# tick-mini-mk-1_0.net
KiCad netlist of a schematic drawn in EAGLE
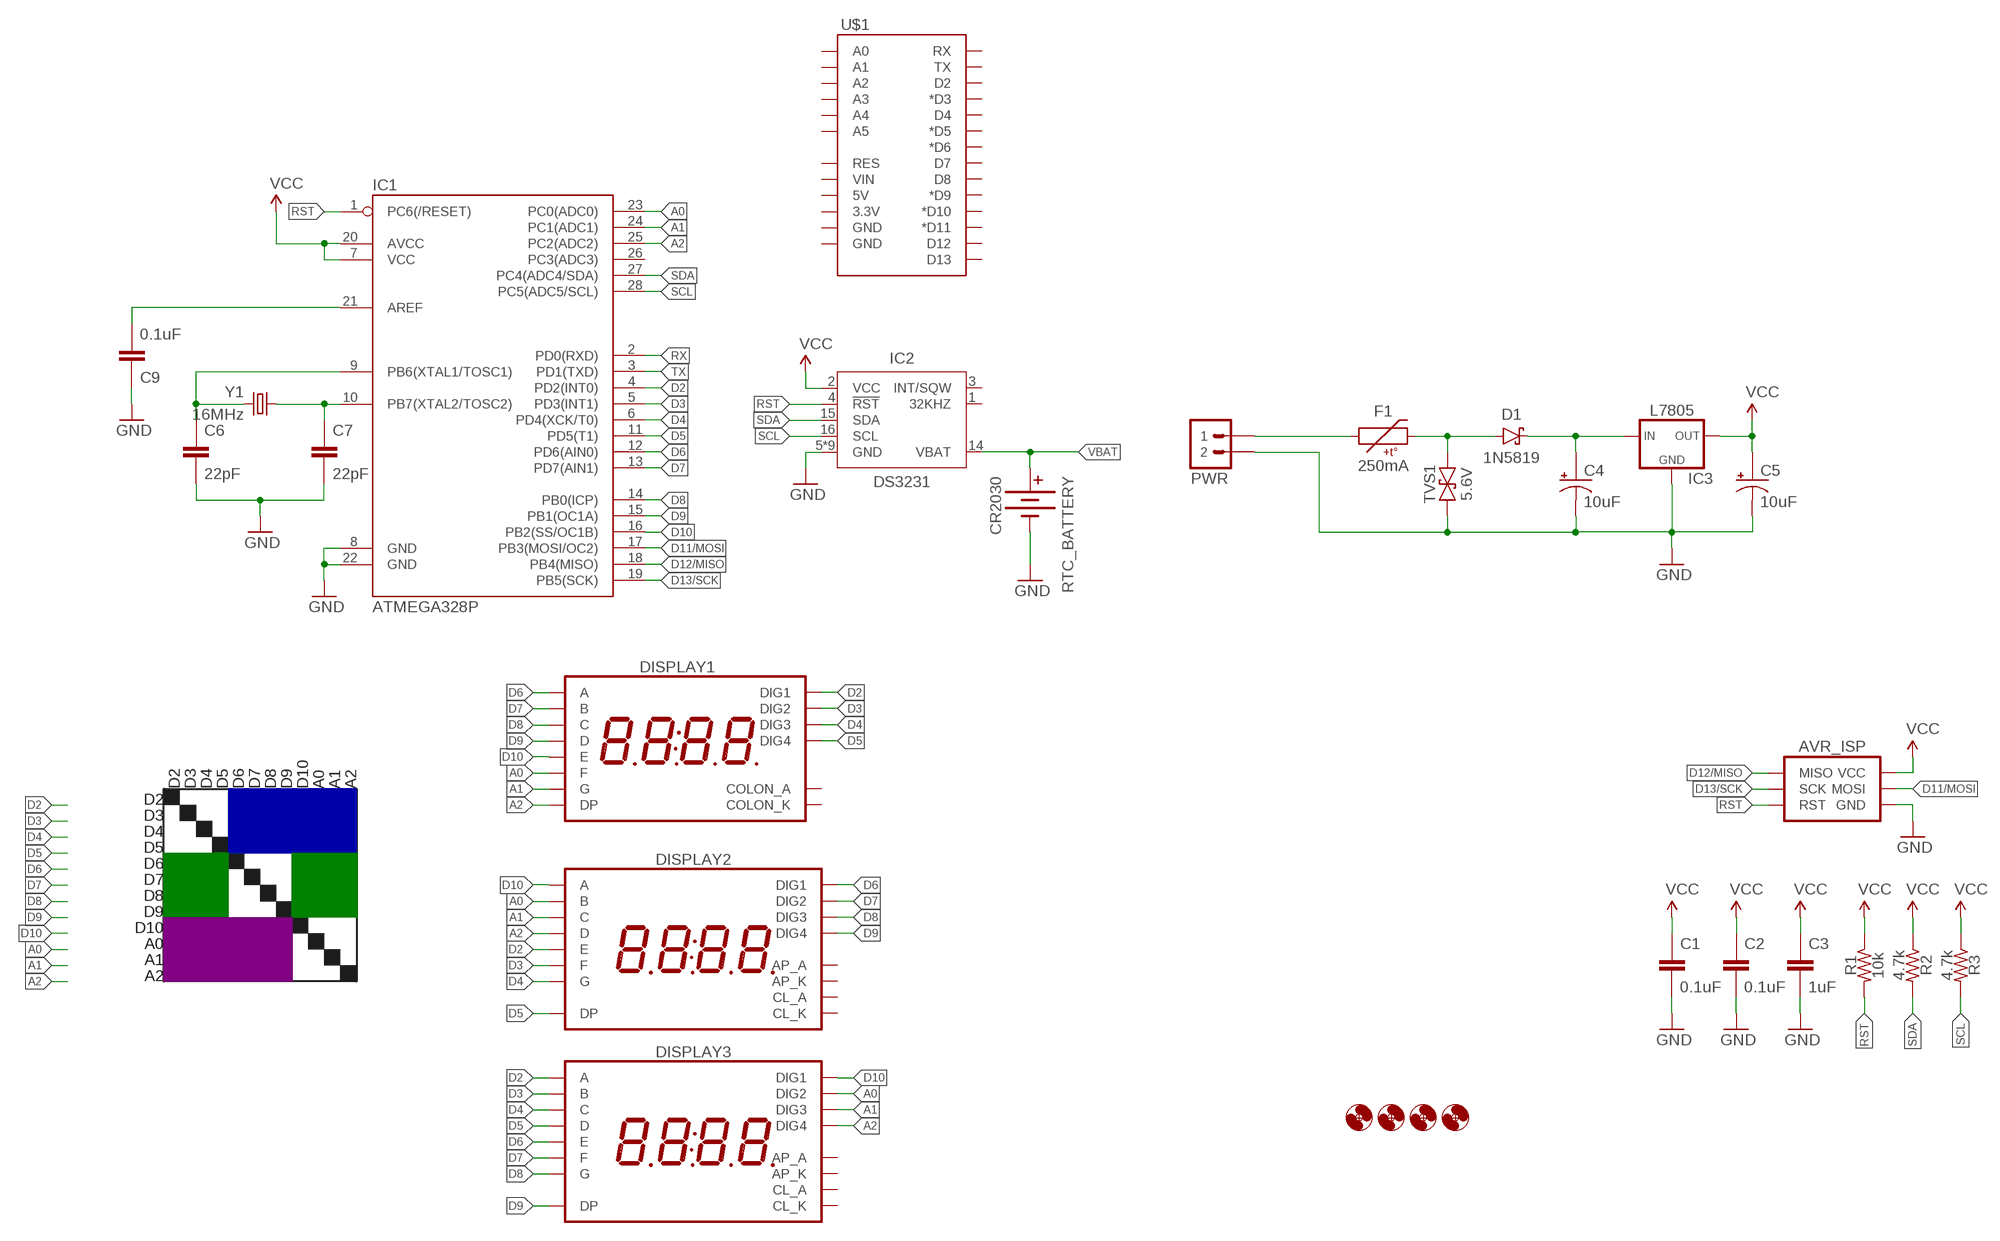
[diagram p0: schematic, sheet 1]

(export (version "E")
  (design (tool "Eeschema 10.0.6"))
  (components
    (comp (ref "AVR_ISP")
      (value "AVR_SPI_PRG_6PTH")
      (footprint "eagle-import:2X3")
      (libsource (lib "eagle-import") (part "AVR_SPI_PRG_6PTH"))
    )
    (comp (ref "C1")
      (value "0.1uF")
      (footprint "eagle-import:C025-024X044")
      (libsource (lib "eagle-import") (part "CAPACITOR-CERAMIC025-024X044"))
    )
    (comp (ref "C2")
      (value "0.1uF")
      (footprint "eagle-import:C025-024X044")
      (libsource (lib "eagle-import") (part "CAPACITOR-CERAMIC025-024X044"))
    )
    (comp (ref "C3")
      (value "1uF")
      (footprint "eagle-import:C025-024X044")
      (libsource (lib "eagle-import") (part "CAPACITOR-CERAMIC025-024X044"))
    )
    (comp (ref "C4")
      (value "10uF")
      (footprint "eagle-import:E2-5")
      (libsource (lib "eagle-import") (part "CAPACITOR-POLARIZEDE2-5"))
    )
    (comp (ref "C5")
      (value "10uF")
      (footprint "eagle-import:E2-5")
      (libsource (lib "eagle-import") (part "CAPACITOR-POLARIZEDE2-5"))
    )
    (comp (ref "C6")
      (value "22pF")
      (footprint "eagle-import:C025-024X044")
      (libsource (lib "eagle-import") (part "CAPACITOR-CERAMIC025-024X044"))
    )
    (comp (ref "C7")
      (value "22pF")
      (footprint "eagle-import:C025-024X044")
      (libsource (lib "eagle-import") (part "CAPACITOR-CERAMIC025-024X044"))
    )
    (comp (ref "C9")
      (value "0.1uF")
      (footprint "eagle-import:C025-024X044")
      (libsource (lib "eagle-import") (part "CAPACITOR-CERAMIC025-024X044"))
    )
    (comp (ref "D1")
      (value "1N5819")
      (footprint "eagle-import:DIODE-10.16MM")
      (libsource (lib "eagle-import") (part "DIODE-SCHOTTKYPTH-10.16MM"))
    )
    (comp (ref "DISPLAY1")
      (value "7SEG_4DIGIT_COLON14.2MM-CC")
      (footprint "eagle-import:7SEG_4DIG_0.56IN_14MM_ADAFRUIT")
      (libsource (lib "eagle-import") (part "7SEG_4DIGIT_COLON14.2MM-CC"))
    )
    (comp (ref "DISPLAY2")
      (value "7SEG_4DIGIT_COLON_APOS")
      (footprint "eagle-import:7SEG_4DIG_10MM")
      (libsource (lib "eagle-import") (part "7SEG_4DIGIT_COLON_APOS"))
    )
    (comp (ref "DISPLAY3")
      (value "7SEG_4DIGIT_COLON_APOS")
      (footprint "eagle-import:7SEG_4DIG_10MM")
      (libsource (lib "eagle-import") (part "7SEG_4DIGIT_COLON_APOS"))
    )
    (comp (ref "F1")
      (value "250mA")
      (footprint "eagle-import:PTC-PTH-5.08MM")
      (libsource (lib "eagle-import") (part "PTCPTH-5.08MM"))
    )
    (comp (ref "H1")
      (value "HOLE#2")
      (footprint "eagle-import:HOLE-#2")
      (libsource (lib "eagle-import") (part "HOLE#2"))
    )
    (comp (ref "H2")
      (value "HOLE#2")
      (footprint "eagle-import:HOLE-#2")
      (libsource (lib "eagle-import") (part "HOLE#2"))
    )
    (comp (ref "H3")
      (value "HOLE#2")
      (footprint "eagle-import:HOLE-#2")
      (libsource (lib "eagle-import") (part "HOLE#2"))
    )
    (comp (ref "H4")
      (value "HOLE#2")
      (footprint "eagle-import:HOLE-#2")
      (libsource (lib "eagle-import") (part "HOLE#2"))
    )
    (comp (ref "IC1")
      (value "ATMEGA328P")
      (footprint "eagle-import:DIL28-3")
      (libsource (lib "eagle-import") (part "ATMEGA328P_PDIP"))
    )
    (comp (ref "IC2")
      (value "DS3231")
      (footprint "eagle-import:SO16W")
      (libsource (lib "eagle-import") (part "DS3231"))
    )
    (comp (ref "IC3")
      (value "L7805")
      (footprint "eagle-import:TO-92-AMMO")
      (libsource (lib "eagle-import") (part "V_REG_78XXTO-92-INLINE"))
    )
    (comp (ref "PWR")
      (value "M02JST-PTH-VERT")
      (footprint "eagle-import:JST-2-PH-VERT-PTH")
      (libsource (lib "eagle-import") (part "M02JST-PTH-VERT"))
    )
    (comp (ref "R1")
      (value "10k")
      (footprint "eagle-import:RESISTOR-AXIAL-PTH-7.62MM")
      (libsource (lib "eagle-import") (part "RESISTORPTH-AXIAL-7.62MM"))
    )
    (comp (ref "R2")
      (value "4.7k")
      (footprint "eagle-import:RESISTOR-AXIAL-PTH-6.35MM")
      (libsource (lib "eagle-import") (part "RESISTORPTH-AXIAL-6.35MM"))
    )
    (comp (ref "R3")
      (value "4.7k")
      (footprint "eagle-import:RESISTOR-AXIAL-PTH-6.35MM")
      (libsource (lib "eagle-import") (part "RESISTORPTH-AXIAL-6.35MM"))
    )
    (comp (ref "RTC_BATTERY")
      (value "CR2030")
      (footprint "eagle-import:BATTCON_12MM")
      (libsource (lib "eagle-import") (part "BATTERY12MM"))
    )
    (comp (ref "TVS1")
      (value "5.6V")
      (footprint "eagle-import:DO-41-TVS-BI-10.16MM")
      (libsource (lib "eagle-import") (part "TVSDO-41-10.16MM"))
    )
    (comp (ref "U$1")
      (value "ARDUINO_SHIELD_SMALLER")
      (footprint "eagle-import:ARDUINO_SHIELD_NOOUTLINE_INSIDE_SMALLER")
      (libsource (lib "eagle-import") (part "ARDUINO_SHIELD_SMALLER"))
    )
    (comp (ref "Y1")
      (value "16MHz")
      (footprint "eagle-import:HC49U-V")
      (libsource (lib "eagle-import") (part "CRYSTALHC49UV"))
    )
  )
  (nets
    (net (code "1") (name "A0") (class "Default")
      (node (ref "DISPLAY1") (pin "P$12") (pinfunction "F_P$12") (pintype "passive"))
      (node (ref "DISPLAY2") (pin "16") (pinfunction "B_16") (pintype "passive"))
      (node (ref "DISPLAY3") (pin "2") (pinfunction "DIG2_2") (pintype "passive"))
      (node (ref "IC1") (pin "23") (pinfunction "PC0(ADC0)_23") (pintype "bidirectional"))
    )
    (net (code "2") (name "A1") (class "Default")
      (node (ref "DISPLAY1") (pin "P$5") (pinfunction "G_P$5") (pintype "passive"))
      (node (ref "DISPLAY2") (pin "13") (pinfunction "C_13") (pintype "passive"))
      (node (ref "DISPLAY3") (pin "6") (pinfunction "DIG3_6") (pintype "passive"))
      (node (ref "IC1") (pin "24") (pinfunction "PC1(ADC1)_24") (pintype "bidirectional"))
    )
    (net (code "3") (name "A2") (class "Default")
      (node (ref "DISPLAY1") (pin "P$3") (pinfunction "DP_P$3") (pintype "passive"))
      (node (ref "DISPLAY2") (pin "3") (pinfunction "D_3") (pintype "passive"))
      (node (ref "DISPLAY3") (pin "8") (pinfunction "DIG4_8") (pintype "passive"))
      (node (ref "IC1") (pin "25") (pinfunction "PC2(ADC2)_25") (pintype "bidirectional"))
    )
    (net (code "4") (name "D2") (class "Default")
      (node (ref "DISPLAY1") (pin "P$14") (pinfunction "DIG1_P$14") (pintype "passive"))
      (node (ref "DISPLAY2") (pin "5") (pinfunction "E_5") (pintype "passive"))
      (node (ref "DISPLAY3") (pin "14") (pinfunction "A_14") (pintype "passive"))
      (node (ref "IC1") (pin "4") (pinfunction "PD2(INT0)_4") (pintype "bidirectional"))
    )
    (net (code "5") (name "D3") (class "Default")
      (node (ref "DISPLAY1") (pin "P$11") (pinfunction "DIG2_P$11") (pintype "passive"))
      (node (ref "DISPLAY2") (pin "11") (pinfunction "F_11") (pintype "passive"))
      (node (ref "DISPLAY3") (pin "16") (pinfunction "B_16") (pintype "passive"))
      (node (ref "IC1") (pin "5") (pinfunction "PD3(INT1)_5") (pintype "bidirectional"))
    )
    (net (code "6") (name "D4") (class "Default")
      (node (ref "DISPLAY1") (pin "P$10") (pinfunction "DIG3_P$10") (pintype "passive"))
      (node (ref "DISPLAY2") (pin "15") (pinfunction "G_15") (pintype "passive"))
      (node (ref "DISPLAY3") (pin "13") (pinfunction "C_13") (pintype "passive"))
      (node (ref "IC1") (pin "6") (pinfunction "PD4(XCK/T0)_6") (pintype "bidirectional"))
    )
    (net (code "7") (name "D5") (class "Default")
      (node (ref "DISPLAY1") (pin "P$6") (pinfunction "DIG4_P$6") (pintype "passive"))
      (node (ref "DISPLAY2") (pin "7") (pinfunction "DP_7") (pintype "passive"))
      (node (ref "DISPLAY3") (pin "3") (pinfunction "D_3") (pintype "passive"))
      (node (ref "IC1") (pin "11") (pinfunction "PD5(T1)_11") (pintype "bidirectional"))
    )
    (net (code "8") (name "D6") (class "Default")
      (node (ref "DISPLAY1") (pin "P$13") (pinfunction "A_P$13") (pintype "passive"))
      (node (ref "DISPLAY2") (pin "1") (pinfunction "DIG1_1") (pintype "passive"))
      (node (ref "DISPLAY3") (pin "5") (pinfunction "E_5") (pintype "passive"))
      (node (ref "IC1") (pin "12") (pinfunction "PD6(AIN0)_12") (pintype "bidirectional"))
    )
    (net (code "9") (name "D7") (class "Default")
      (node (ref "DISPLAY1") (pin "P$9") (pinfunction "B_P$9") (pintype "passive"))
      (node (ref "DISPLAY2") (pin "2") (pinfunction "DIG2_2") (pintype "passive"))
      (node (ref "DISPLAY3") (pin "11") (pinfunction "F_11") (pintype "passive"))
      (node (ref "IC1") (pin "13") (pinfunction "PD7(AIN1)_13") (pintype "bidirectional"))
    )
    (net (code "10") (name "D8") (class "Default")
      (node (ref "DISPLAY1") (pin "P$4") (pinfunction "C_P$4") (pintype "passive"))
      (node (ref "DISPLAY2") (pin "6") (pinfunction "DIG3_6") (pintype "passive"))
      (node (ref "DISPLAY3") (pin "15") (pinfunction "G_15") (pintype "passive"))
      (node (ref "IC1") (pin "14") (pinfunction "PB0(ICP)_14") (pintype "bidirectional"))
    )
    (net (code "11") (name "D9") (class "Default")
      (node (ref "DISPLAY1") (pin "P$2") (pinfunction "D_P$2") (pintype "passive"))
      (node (ref "DISPLAY2") (pin "8") (pinfunction "DIG4_8") (pintype "passive"))
      (node (ref "DISPLAY3") (pin "7") (pinfunction "DP_7") (pintype "passive"))
      (node (ref "IC1") (pin "15") (pinfunction "PB1(OC1A)_15") (pintype "bidirectional"))
    )
    (net (code "12") (name "D10") (class "Default")
      (node (ref "DISPLAY1") (pin "P$1") (pinfunction "E_P$1") (pintype "passive"))
      (node (ref "DISPLAY2") (pin "14") (pinfunction "A_14") (pintype "passive"))
      (node (ref "DISPLAY3") (pin "1") (pinfunction "DIG1_1") (pintype "passive"))
      (node (ref "IC1") (pin "16") (pinfunction "PB2(SS/OC1B)_16") (pintype "bidirectional"))
    )
    (net (code "13") (name "D11{slash}MOSI") (class "Default")
      (node (ref "AVR_ISP") (pin "4") (pinfunction "MOSI_4") (pintype "passive"))
      (node (ref "IC1") (pin "17") (pinfunction "PB3(MOSI/OC2)_17") (pintype "bidirectional"))
    )
    (net (code "14") (name "D12{slash}MISO") (class "Default")
      (node (ref "AVR_ISP") (pin "1") (pinfunction "MISO_1") (pintype "passive"))
      (node (ref "IC1") (pin "18") (pinfunction "PB4(MISO)_18") (pintype "bidirectional"))
    )
    (net (code "15") (name "D13{slash}SCK") (class "Default")
      (node (ref "AVR_ISP") (pin "3") (pinfunction "SCK_3") (pintype "passive"))
      (node (ref "IC1") (pin "19") (pinfunction "PB5(SCK)_19") (pintype "bidirectional"))
    )
    (net (code "16") (name "GND") (class "Default")
      (node (ref "AVR_ISP") (pin "6") (pinfunction "GND_6") (pintype "passive"))
      (node (ref "C1") (pin "2") (pinfunction "2_2") (pintype "passive"))
      (node (ref "C2") (pin "2") (pinfunction "2_2") (pintype "passive"))
      (node (ref "C3") (pin "2") (pinfunction "2_2") (pintype "passive"))
      (node (ref "C4") (pin "-") (pinfunction "-_-") (pintype "passive"))
      (node (ref "C5") (pin "-") (pinfunction "-_-") (pintype "passive"))
      (node (ref "C6") (pin "2") (pinfunction "2_2") (pintype "passive"))
      (node (ref "C7") (pin "2") (pinfunction "2_2") (pintype "passive"))
      (node (ref "C9") (pin "1") (pinfunction "1_1") (pintype "passive"))
      (node (ref "IC1") (pin "22") (pinfunction "GND_22") (pintype "bidirectional"))
      (node (ref "IC1") (pin "8") (pinfunction "GND_8") (pintype "bidirectional"))
      (node (ref "IC2") (pin "10") (pinfunction "GND_10") (pintype "bidirectional"))
      (node (ref "IC2") (pin "11") (pinfunction "GND_11") (pintype "bidirectional"))
      (node (ref "IC2") (pin "12") (pinfunction "GND_12") (pintype "bidirectional"))
      (node (ref "IC2") (pin "13") (pinfunction "GND_13") (pintype "bidirectional"))
      (node (ref "IC2") (pin "5") (pinfunction "GND_5") (pintype "bidirectional"))
      (node (ref "IC2") (pin "6") (pinfunction "GND_6") (pintype "bidirectional"))
      (node (ref "IC2") (pin "7") (pinfunction "GND_7") (pintype "bidirectional"))
      (node (ref "IC2") (pin "8") (pinfunction "GND_8") (pintype "bidirectional"))
      (node (ref "IC2") (pin "9") (pinfunction "GND_9") (pintype "bidirectional"))
      (node (ref "IC3") (pin "2") (pinfunction "GND_2") (pintype "bidirectional"))
      (node (ref "PWR") (pin "2") (pinfunction "2_2") (pintype "passive"))
      (node (ref "RTC_BATTERY") (pin "GND") (pinfunction "-_GND") (pintype "power_in"))
      (node (ref "TVS1") (pin "P$1") (pinfunction "1_P$1") (pintype "passive"))
    )
    (net (code "17") (name "Net-(F1-1)") (class "Default")
      (node (ref "F1") (pin "P$1") (pinfunction "1_P$1") (pintype "passive"))
      (node (ref "PWR") (pin "1") (pinfunction "1_1") (pintype "passive"))
    )
    (net (code "18") (name "Net-(F1-2)") (class "Default")
      (node (ref "D1") (pin "A") (pinfunction "A_A") (pintype "passive"))
      (node (ref "F1") (pin "P$2") (pinfunction "2_P$2") (pintype "passive"))
      (node (ref "TVS1") (pin "P$2") (pinfunction "2_P$2") (pintype "passive"))
    )
    (net (code "19") (name "Net-(IC1-AREF)") (class "Default")
      (node (ref "C9") (pin "2") (pinfunction "2_2") (pintype "passive"))
      (node (ref "IC1") (pin "21") (pinfunction "AREF_21") (pintype "bidirectional"))
    )
    (net (code "20") (name "Net-(IC1-PB6(XTAL1{slash}TOSC1))") (class "Default")
      (node (ref "C6") (pin "1") (pinfunction "1_1") (pintype "passive"))
      (node (ref "IC1") (pin "9") (pinfunction "PB6(XTAL1/TOSC1)_9") (pintype "bidirectional"))
      (node (ref "Y1") (pin "2") (pinfunction "2_2") (pintype "passive"))
    )
    (net (code "21") (name "Net-(IC1-PB7(XTAL2{slash}TOSC2))") (class "Default")
      (node (ref "C7") (pin "1") (pinfunction "1_1") (pintype "passive"))
      (node (ref "IC1") (pin "10") (pinfunction "PB7(XTAL2/TOSC2)_10") (pintype "bidirectional"))
      (node (ref "Y1") (pin "1") (pinfunction "1_1") (pintype "passive"))
    )
    (net (code "22") (name "Net-(IC3-IN)") (class "Default")
      (node (ref "C4") (pin "+") (pinfunction "+_+") (pintype "passive"))
      (node (ref "D1") (pin "C") (pinfunction "C_C") (pintype "passive"))
      (node (ref "IC3") (pin "1") (pinfunction "IN_1") (pintype "bidirectional"))
    )
    (net (code "23") (name "RST") (class "Default")
      (node (ref "AVR_ISP") (pin "5") (pinfunction "RST_5") (pintype "passive"))
      (node (ref "IC1") (pin "1") (pinfunction "PC6(/RESET)_1") (pintype "bidirectional"))
      (node (ref "IC2") (pin "4") (pinfunction "~{RST}_4") (pintype "bidirectional"))
      (node (ref "R1") (pin "P$2") (pinfunction "2_P$2") (pintype "passive"))
    )
    (net (code "24") (name "RX") (class "Default")
      (node (ref "IC1") (pin "2") (pinfunction "PD0(RXD)_2") (pintype "bidirectional"))
    )
    (net (code "25") (name "SCL") (class "Default")
      (node (ref "IC1") (pin "28") (pinfunction "PC5(ADC5/SCL)_28") (pintype "bidirectional"))
      (node (ref "IC2") (pin "16") (pinfunction "SCL_16") (pintype "bidirectional"))
      (node (ref "R3") (pin "P$2") (pinfunction "2_P$2") (pintype "passive"))
    )
    (net (code "26") (name "SDA") (class "Default")
      (node (ref "IC1") (pin "27") (pinfunction "PC4(ADC4/SDA)_27") (pintype "bidirectional"))
      (node (ref "IC2") (pin "15") (pinfunction "SDA_15") (pintype "bidirectional"))
      (node (ref "R2") (pin "P$2") (pinfunction "2_P$2") (pintype "passive"))
    )
    (net (code "27") (name "TX") (class "Default")
      (node (ref "IC1") (pin "3") (pinfunction "PD1(TXD)_3") (pintype "bidirectional"))
    )
    (net (code "28") (name "VBAT") (class "Default")
      (node (ref "IC2") (pin "14") (pinfunction "VBAT_14") (pintype "bidirectional"))
      (node (ref "RTC_BATTERY") (pin "PWR@1") (pinfunction "+_PWR@1") (pintype "power_in"))
    )
    (net (code "29") (name "VCC") (class "Default")
      (node (ref "AVR_ISP") (pin "2") (pinfunction "VCC_2") (pintype "passive"))
      (node (ref "C1") (pin "1") (pinfunction "1_1") (pintype "passive"))
      (node (ref "C2") (pin "1") (pinfunction "1_1") (pintype "passive"))
      (node (ref "C3") (pin "1") (pinfunction "1_1") (pintype "passive"))
      (node (ref "C5") (pin "+") (pinfunction "+_+") (pintype "passive"))
      (node (ref "IC1") (pin "20") (pinfunction "AVCC_20") (pintype "bidirectional"))
      (node (ref "IC1") (pin "7") (pinfunction "VCC_7") (pintype "bidirectional"))
      (node (ref "IC2") (pin "2") (pinfunction "VCC_2") (pintype "bidirectional"))
      (node (ref "IC3") (pin "3") (pinfunction "OUT_3") (pintype "bidirectional"))
      (node (ref "R1") (pin "P$1") (pinfunction "1_P$1") (pintype "passive"))
      (node (ref "R2") (pin "P$1") (pinfunction "1_P$1") (pintype "passive"))
      (node (ref "R3") (pin "P$1") (pinfunction "1_P$1") (pintype "passive"))
    )
    (net (code "30") (name "unconnected-(DISPLAY1-COLON_A-PadP$8)") (class "Default")
      (node (ref "DISPLAY1") (pin "P$8") (pinfunction "COLON_A_P$8") (pintype "passive"))
    )
    (net (code "31") (name "unconnected-(DISPLAY1-COLON_K-PadP$7)") (class "Default")
      (node (ref "DISPLAY1") (pin "P$7") (pinfunction "COLON_K_P$7") (pintype "passive"))
    )
    (net (code "32") (name "unconnected-(DISPLAY2-AP_A-Pad10)") (class "Default")
      (node (ref "DISPLAY2") (pin "10") (pinfunction "AP_A_10") (pintype "bidirectional"))
    )
    (net (code "33") (name "unconnected-(DISPLAY2-AP_K-Pad9)") (class "Default")
      (node (ref "DISPLAY2") (pin "9") (pinfunction "AP_K_9") (pintype "bidirectional"))
    )
    (net (code "34") (name "unconnected-(DISPLAY2-CL_A-Pad4)") (class "Default")
      (node (ref "DISPLAY2") (pin "4") (pinfunction "CL_A_4") (pintype "passive"))
    )
    (net (code "35") (name "unconnected-(DISPLAY2-CL_K-Pad12)") (class "Default")
      (node (ref "DISPLAY2") (pin "12") (pinfunction "CL_K_12") (pintype "passive"))
    )
    (net (code "36") (name "unconnected-(DISPLAY3-AP_A-Pad10)") (class "Default")
      (node (ref "DISPLAY3") (pin "10") (pinfunction "AP_A_10") (pintype "bidirectional"))
    )
    (net (code "37") (name "unconnected-(DISPLAY3-AP_K-Pad9)") (class "Default")
      (node (ref "DISPLAY3") (pin "9") (pinfunction "AP_K_9") (pintype "bidirectional"))
    )
    (net (code "38") (name "unconnected-(DISPLAY3-CL_A-Pad4)") (class "Default")
      (node (ref "DISPLAY3") (pin "4") (pinfunction "CL_A_4") (pintype "passive"))
    )
    (net (code "39") (name "unconnected-(DISPLAY3-CL_K-Pad12)") (class "Default")
      (node (ref "DISPLAY3") (pin "12") (pinfunction "CL_K_12") (pintype "passive"))
    )
    (net (code "40") (name "unconnected-(IC1-PC3(ADC3)-Pad26)") (class "Default")
      (node (ref "IC1") (pin "26") (pinfunction "PC3(ADC3)_26") (pintype "bidirectional"))
    )
    (net (code "41") (name "unconnected-(IC2-32KHZ-Pad1)") (class "Default")
      (node (ref "IC2") (pin "1") (pinfunction "32KHZ_1") (pintype "bidirectional"))
    )
    (net (code "42") (name "unconnected-(IC2-INT{slash}SQW-Pad3)") (class "Default")
      (node (ref "IC2") (pin "3") (pinfunction "INT/SQW_3") (pintype "bidirectional"))
    )
    (net (code "43") (name "unconnected-(U$1-*D3-PadD3)") (class "Default")
      (node (ref "U$1") (pin "D3") (pinfunction "*D3_D3") (pintype "bidirectional"))
    )
    (net (code "44") (name "unconnected-(U$1-*D5-PadD5)") (class "Default")
      (node (ref "U$1") (pin "D5") (pinfunction "*D5_D5") (pintype "bidirectional"))
    )
    (net (code "45") (name "unconnected-(U$1-*D6-PadD6)") (class "Default")
      (node (ref "U$1") (pin "D6") (pinfunction "*D6_D6") (pintype "bidirectional"))
    )
    (net (code "46") (name "unconnected-(U$1-*D9-PadD9)") (class "Default")
      (node (ref "U$1") (pin "D9") (pinfunction "*D9_D9") (pintype "bidirectional"))
    )
    (net (code "47") (name "unconnected-(U$1-*D10-PadD10)") (class "Default")
      (node (ref "U$1") (pin "D10") (pinfunction "*D10_D10") (pintype "bidirectional"))
    )
    (net (code "48") (name "unconnected-(U$1-*D11-PadD11)") (class "Default")
      (node (ref "U$1") (pin "D11") (pinfunction "*D11_D11") (pintype "bidirectional"))
    )
    (net (code "49") (name "unconnected-(U$1-GND-PadGND@0)") (class "Default")
      (node (ref "U$1") (pin "GND@0") (pinfunction "GND_GND@0") (pintype "bidirectional"))
    )
    (net (code "50") (name "unconnected-(U$1-GND-PadGND@1)") (class "Default")
      (node (ref "U$1") (pin "GND@1") (pinfunction "GND_GND@1") (pintype "bidirectional"))
    )
    (net (code "51") (name "unconnected-(U$1-Pad3.3V)") (class "Default")
      (node (ref "U$1") (pin "3.3V") (pinfunction "3.3V_3.3V") (pintype "bidirectional"))
    )
    (net (code "52") (name "unconnected-(U$1-Pad5V)") (class "Default")
      (node (ref "U$1") (pin "5V") (pinfunction "5V_5V") (pintype "bidirectional"))
    )
    (net (code "53") (name "unconnected-(U$1-PadA0)") (class "Default")
      (node (ref "U$1") (pin "A0") (pinfunction "A0_A0") (pintype "bidirectional"))
    )
    (net (code "54") (name "unconnected-(U$1-PadA1)") (class "Default")
      (node (ref "U$1") (pin "A1") (pinfunction "A1_A1") (pintype "bidirectional"))
    )
    (net (code "55") (name "unconnected-(U$1-PadA2)") (class "Default")
      (node (ref "U$1") (pin "A2") (pinfunction "A2_A2") (pintype "bidirectional"))
    )
    (net (code "56") (name "unconnected-(U$1-PadA3)") (class "Default")
      (node (ref "U$1") (pin "A3") (pinfunction "A3_A3") (pintype "bidirectional"))
    )
    (net (code "57") (name "unconnected-(U$1-PadA4)") (class "Default")
      (node (ref "U$1") (pin "A4") (pinfunction "A4_A4") (pintype "bidirectional"))
    )
    (net (code "58") (name "unconnected-(U$1-PadA5)") (class "Default")
      (node (ref "U$1") (pin "A5") (pinfunction "A5_A5") (pintype "bidirectional"))
    )
    (net (code "59") (name "unconnected-(U$1-PadD2)") (class "Default")
      (node (ref "U$1") (pin "D2") (pinfunction "D2_D2") (pintype "bidirectional"))
    )
    (net (code "60") (name "unconnected-(U$1-PadD4)") (class "Default")
      (node (ref "U$1") (pin "D4") (pinfunction "D4_D4") (pintype "bidirectional"))
    )
    (net (code "61") (name "unconnected-(U$1-PadD7)") (class "Default")
      (node (ref "U$1") (pin "D7") (pinfunction "D7_D7") (pintype "bidirectional"))
    )
    (net (code "62") (name "unconnected-(U$1-PadD8)") (class "Default")
      (node (ref "U$1") (pin "D8") (pinfunction "D8_D8") (pintype "bidirectional"))
    )
    (net (code "63") (name "unconnected-(U$1-PadD12)") (class "Default")
      (node (ref "U$1") (pin "D12") (pinfunction "D12_D12") (pintype "bidirectional"))
    )
    (net (code "64") (name "unconnected-(U$1-PadD13)") (class "Default")
      (node (ref "U$1") (pin "D13") (pinfunction "D13_D13") (pintype "bidirectional"))
    )
    (net (code "65") (name "unconnected-(U$1-PadRES)") (class "Default")
      (node (ref "U$1") (pin "RES") (pinfunction "RES_RES") (pintype "bidirectional"))
    )
    (net (code "66") (name "unconnected-(U$1-PadRX)") (class "Default")
      (node (ref "U$1") (pin "RX") (pinfunction "RX_RX") (pintype "bidirectional"))
    )
    (net (code "67") (name "unconnected-(U$1-PadTX)") (class "Default")
      (node (ref "U$1") (pin "TX") (pinfunction "TX_TX") (pintype "bidirectional"))
    )
    (net (code "68") (name "unconnected-(U$1-PadVIN)") (class "Default")
      (node (ref "U$1") (pin "VIN") (pinfunction "VIN_VIN") (pintype "bidirectional"))
    )
  )
)
